# MPBoard_L1_PWR_ext.net
KiCad netlist of a schematic drawn in Altium Designer
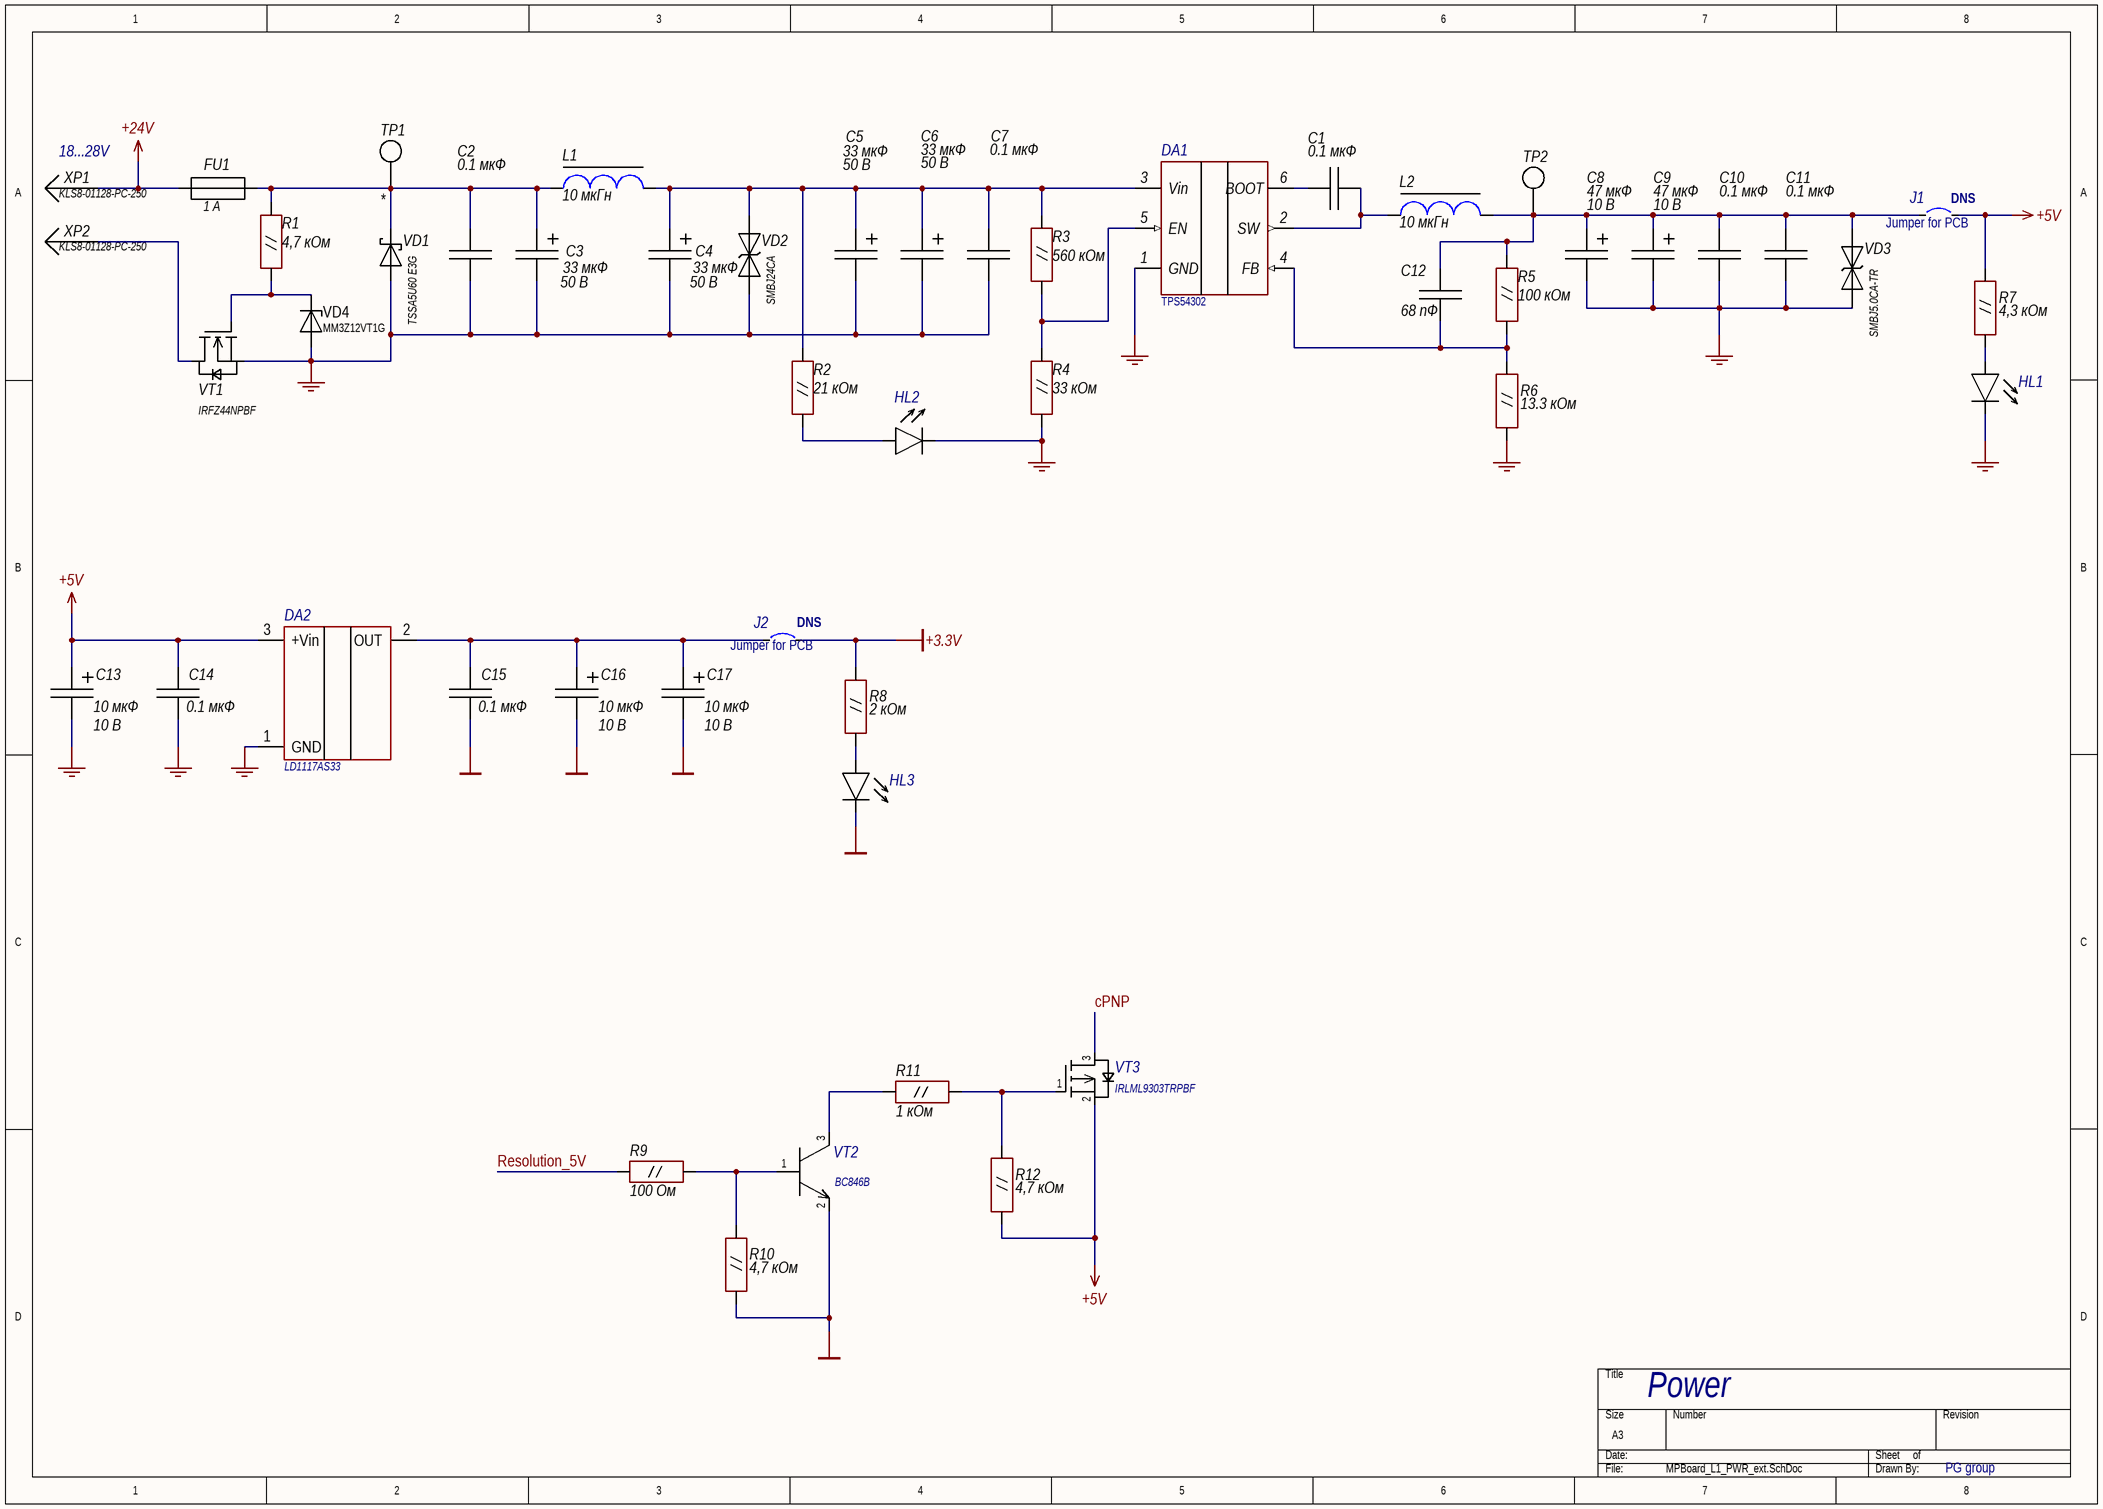
[diagram p0: MPBoard_L1_PWR_ext.SchDoc]

(export (version "E")
  (design (tool "Eeschema 10.0.6"))
  (components
    (comp (ref "C1")
      (value "0.1 мкФ")
      (footprint "CAP-0805")
      (description "Конденсатор")
      (fields (field (name "MF") "KEMET") (field (name "TOLERANCE") "± 10 %"))
      (libsource (lib "MainBoard") (part "C"))
    )
    (comp (ref "C2")
      (value "0.1 мкФ")
      (footprint "CAP-0805")
      (description "Конденсатор")
      (fields (field (name "MF") "KEMET") (field (name "TOLERANCE") "± 10 %"))
      (libsource (lib "MainBoard") (part "C"))
    )
    (comp (ref "C3")
      (value "33 мкФ")
      (footprint "CAPAE-103")
      (description "Конденсатор полярный")
      (fields (field (name "MF") "KEMET") (field (name "TOLERANCE") "± 10 %") (field (name "VOLTAGE") "50 В"))
      (libsource (lib "MainBoard") (part "C_POLAR"))
    )
    (comp (ref "C4")
      (value "33 мкФ")
      (footprint "CAPAE-103")
      (description "Конденсатор полярный")
      (fields (field (name "MF") "KEMET") (field (name "TOLERANCE") "± 10 %") (field (name "VOLTAGE") "50 В"))
      (libsource (lib "MainBoard") (part "C_POLAR"))
    )
    (comp (ref "C5")
      (value "33 мкФ")
      (footprint "CAPAE-103")
      (description "Конденсатор полярный")
      (fields (field (name "MF") "KEMET") (field (name "TOLERANCE") "± 10 %") (field (name "VOLTAGE") "50 В"))
      (libsource (lib "MainBoard") (part "C_POLAR"))
    )
    (comp (ref "C6")
      (value "33 мкФ")
      (footprint "CAPAE-103")
      (description "Конденсатор полярный")
      (fields (field (name "MF") "KEMET") (field (name "TOLERANCE") "± 10 %") (field (name "VOLTAGE") "50 В"))
      (libsource (lib "MainBoard") (part "C_POLAR"))
    )
    (comp (ref "C7")
      (value "0.1 мкФ")
      (footprint "CAP-0805")
      (description "Конденсатор")
      (fields (field (name "MF") "KEMET") (field (name "TOLERANCE") "± 10 %"))
      (libsource (lib "MainBoard") (part "C"))
    )
    (comp (ref "C8")
      (value "47 мкФ")
      (footprint "CAPMP-3528")
      (description "Конденсатор полярный\r\nтантал")
      (fields (field (name "MF") "KEMET") (field (name "TOLERANCE") "± 10 %") (field (name "VOLTAGE") "10 В"))
      (libsource (lib "MainBoard") (part "C_POLAR"))
    )
    (comp (ref "C9")
      (value "47 мкФ")
      (footprint "CAPMP-3528")
      (description "Конденсатор полярный\r\nтантал")
      (fields (field (name "MF") "KEMET") (field (name "TOLERANCE") "± 10 %") (field (name "VOLTAGE") "10 В"))
      (libsource (lib "MainBoard") (part "C_POLAR"))
    )
    (comp (ref "C10")
      (value "0.1 мкФ")
      (footprint "CAP-0805")
      (description "Конденсатор")
      (fields (field (name "MF") "KEMET") (field (name "TOLERANCE") "± 10 %"))
      (libsource (lib "MainBoard") (part "C"))
    )
    (comp (ref "C11")
      (value "0.1 мкФ")
      (footprint "CAP-0805")
      (description "Конденсатор")
      (fields (field (name "MF") "KEMET") (field (name "TOLERANCE") "± 10 %"))
      (libsource (lib "MainBoard") (part "C"))
    )
    (comp (ref "C12")
      (value "68 пФ")
      (footprint "CAP-0805")
      (description "Конденсатор")
      (fields (field (name "MF") "KEMET") (field (name "TOLERANCE") "± 5 %"))
      (libsource (lib "MainBoard") (part "C"))
    )
    (comp (ref "C13")
      (value "10 мкФ")
      (footprint "CAPMP-3528")
      (description "Конденсатор полярный\r\nтантал")
      (fields (field (name "MF") "KEMET") (field (name "TOLERANCE") "± 10 %") (field (name "VOLTAGE") "10 В"))
      (libsource (lib "MainBoard") (part "C_POLAR"))
    )
    (comp (ref "C14")
      (value "0.1 мкФ")
      (footprint "CAP-0805")
      (description "Конденсатор")
      (fields (field (name "MF") "KEMET") (field (name "TOLERANCE") "± 10 %"))
      (libsource (lib "MainBoard") (part "C"))
    )
    (comp (ref "C15")
      (value "0.1 мкФ")
      (footprint "CAP-0805")
      (description "Конденсатор")
      (fields (field (name "MF") "KEMET") (field (name "TOLERANCE") "± 10 %"))
      (libsource (lib "MainBoard") (part "C"))
    )
    (comp (ref "C16")
      (value "10 мкФ")
      (footprint "CAPMP-3528")
      (description "Конденсатор полярный\r\nтантал")
      (fields (field (name "MF") "KEMET") (field (name "TOLERANCE") "± 10 %") (field (name "VOLTAGE") "10 В"))
      (libsource (lib "MainBoard") (part "C_POLAR"))
    )
    (comp (ref "C17")
      (value "10 мкФ")
      (footprint "CAPMP-3528")
      (description "Конденсатор полярный\r\nтантал")
      (fields (field (name "MF") "KEMET") (field (name "TOLERANCE") "± 10 %") (field (name "VOLTAGE") "10 В"))
      (libsource (lib "MainBoard") (part "C_POLAR"))
    )
    (comp (ref "DA1")
      (value "TPS54302")
      (footprint "SOT23-6")
      (description "DC/DC Buck")
      (fields (field (name "MF") "Texas Instruments") (field (name "MFPARTNUM") "TPS54302DDCR"))
      (libsource (lib "MPBoard") (part "DA_TPS54302"))
    )
    (comp (ref "DA2")
      (value "LD1117AS33")
      (footprint "SOT-223 LD1117")
      (description "Linear Regulator 3.3V")
      (fields (field (name "MF") "STMicroelectronics") (field (name "MFPARTNUM") "LD1117AS33TR"))
      (libsource (lib "MPBoard") (part "DA_LD1117AS33"))
    )
    (comp (ref "FU1")
      (value "1 A")
      (footprint "FUSE HOLDERS B 5X20")
      (description "Предохранитель")
      (fields (field (name "MFPARTNUM") "RND 170-00190"))
      (libsource (lib "MPBoard") (part "FU"))
    )
    (comp (ref "HL1")
      (value "Blue")
      (footprint "CH0805LB")
      (description "Светодиод")
      (fields (field (name "MF") "Foryard") (field (name "MFPARTNUM") "FYLS-0805UBC"))
      (libsource (lib "MPBoard") (part "VD_LED"))
    )
    (comp (ref "HL2")
      (value "Red")
      (footprint "CH0805LR")
      (description "Светодиод")
      (fields (field (name "MF") "Foryard") (field (name "MFPARTNUM") "FYLS-0805URC"))
      (libsource (lib "MPBoard") (part "VD_LED"))
    )
    (comp (ref "HL3")
      (value "Green")
      (footprint "CH0805LG")
      (description "Светодиод")
      (fields (field (name "MF") "Foryard") (field (name "MFPARTNUM") "FYLS-0805UGC"))
      (libsource (lib "MPBoard") (part "VD_LED"))
    )
    (comp (ref "J1")
      (value "Jumper for PCB")
      (footprint "JUMPER-SMD min")
      (description "Перемычка на плату")
      (libsource (lib "MPBoard") (part "Jumper"))
    )
    (comp (ref "J2")
      (value "Jumper for PCB")
      (footprint "JUMPER-SMD min")
      (description "Перемычка на плату")
      (libsource (lib "MPBoard") (part "Jumper"))
    )
    (comp (ref "L1")
      (value "10 мкГн")
      (footprint "IND_IHLP2525")
      (description "Индуктивность")
      (fields (field (name "MF") "Vishay") (field (name "MFPARTNUM") "IHLP2525EZER100M01"))
      (libsource (lib "MainBoard") (part "L_CORE"))
    )
    (comp (ref "L2")
      (value "10 мкГн")
      (footprint "IND_IHLP2525")
      (description "Индуктивность")
      (fields (field (name "MF") "Vishay") (field (name "MFPARTNUM") "IHLP2525EZER100M01"))
      (libsource (lib "MainBoard") (part "L_CORE"))
    )
    (comp (ref "R1")
      (value "4,7 кОм")
      (footprint "RES-0805")
      (description "Резистор 0.125 W")
      (fields (field (name "MF") "Vishay") (field (name "TOLERANCE") "± 1 %"))
      (libsource (lib "MainBoard") (part "R_0.125W"))
    )
    (comp (ref "R2")
      (value "21 кОм")
      (footprint "RES-0805")
      (description "Резистор 0.125 W")
      (fields (field (name "MF") "Vishay") (field (name "TOLERANCE") "± 1 %"))
      (libsource (lib "MainBoard") (part "R_0.125W"))
    )
    (comp (ref "R3")
      (value "560 кОм")
      (footprint "RES-0805")
      (description "Резистор 0.125 W")
      (fields (field (name "MF") "Vishay") (field (name "TOLERANCE") "± 5 %"))
      (libsource (lib "") (part "R_0.125W_2"))
    )
    (comp (ref "R4")
      (value "33 кОм")
      (footprint "RES-0805")
      (description "Резистор 0.125 W")
      (fields (field (name "MF") "Vishay") (field (name "TOLERANCE") "± 5 %"))
      (libsource (lib "") (part "R_0.125W_2"))
    )
    (comp (ref "R5")
      (value "100 кОм")
      (footprint "RES-0805")
      (description "Резистор 0.125 W")
      (fields (field (name "MF") "Vishay") (field (name "TOLERANCE") "± 5 %"))
      (libsource (lib "") (part "R_0.125W_2"))
    )
    (comp (ref "R6")
      (value "13.3 кОм")
      (footprint "RES-0805")
      (description "Резистор 0.125 W")
      (fields (field (name "MF") "Vishay") (field (name "TOLERANCE") "± 1 %"))
      (libsource (lib "") (part "R_0.125W_2"))
    )
    (comp (ref "R7")
      (value "4,3 кОм")
      (footprint "RES-0805")
      (description "Резистор 0.125 W")
      (fields (field (name "MF") "Vishay") (field (name "TOLERANCE") "± 1 %"))
      (libsource (lib "") (part "R_0.125W_2"))
    )
    (comp (ref "R8")
      (value "2 кОм")
      (footprint "RES-0805")
      (description "Резистор 0.125 W")
      (fields (field (name "MF") "Vishay") (field (name "TOLERANCE") "± 1 %"))
      (libsource (lib "") (part "R_0.125W_2"))
    )
    (comp (ref "R9")
      (value "100 Ом")
      (footprint "RES-0805")
      (description "Резистор 0.125 W")
      (fields (field (name "MF") "Vishay") (field (name "TOLERANCE") "± 1 %"))
      (libsource (lib "") (part "R_0.125W_1"))
    )
    (comp (ref "R10")
      (value "4,7 кОм")
      (footprint "RES-0805")
      (description "Резистор 0.125 W")
      (fields (field (name "MF") "Vishay") (field (name "TOLERANCE") "± 1 %"))
      (libsource (lib "") (part "R_0.125W_2"))
    )
    (comp (ref "R11")
      (value "1 кОм")
      (footprint "RES-0805")
      (description "Резистор 0.125 W")
      (fields (field (name "MF") "Vishay") (field (name "TOLERANCE") "± 1 %"))
      (libsource (lib "") (part "R_0.125W_1"))
    )
    (comp (ref "R12")
      (value "4,7 кОм")
      (footprint "RES-0805")
      (description "Резистор 0.125 W")
      (fields (field (name "MF") "Vishay") (field (name "TOLERANCE") "± 1 %"))
      (libsource (lib "") (part "R_0.125W_2"))
    )
    (comp (ref "TP1")
      (value "*")
      (footprint "TP_1.5")
      (description "Test Point")
      (libsource (lib "MainBoard") (part "TEST_POINT"))
    )
    (comp (ref "TP2")
      (value "*")
      (footprint "TP_1.5")
      (description "Test Point")
      (libsource (lib "MainBoard") (part "TEST_POINT"))
    )
    (comp (ref "VD1")
      (value "TSSA5U60 E3G")
      (footprint "DIODE SMA")
      (description "Диод Шоттки")
      (fields (field (name "MF") "Taiwan Semiconductor"))
      (libsource (lib "MainBoard") (part "VD_SHOTTKY"))
    )
    (comp (ref "VD2")
      (value "SMBJ24CA")
      (footprint "DIODE SMB")
      (description "Супрессор")
      (fields (field (name "MF") "STMicroelectronics"))
      (libsource (lib "MainBoard") (part "VD_TVS_BIDIR"))
    )
    (comp (ref "VD3")
      (value "SMBJ5.0CA-TR")
      (footprint "DIODE SMB")
      (description "Супрессор")
      (fields (field (name "MF") "STMicroelectronics") (field (name "IPSPARTNUMBER") "300-34-034"))
      (libsource (lib "MainBoard") (part "VD_TVS_BIDIR"))
    )
    (comp (ref "VD4")
      (value "MM3Z12VT1G")
      (footprint "SOD-323")
      (description "Стабилитрон")
      (fields (field (name "MF") "Nexperia"))
      (libsource (lib "MainBoard") (part "VD_ZENER"))
    )
    (comp (ref "VT1")
      (value "IRFZ44NPBF")
      (footprint "TO220S inline")
      (description "MOSFET")
      (fields (field (name "MF") "Infineon Technologies"))
      (libsource (lib "MainBoard") (part "VT_N-MOSFET"))
    )
    (comp (ref "VT2")
      (value "BC846B")
      (footprint "SOT23")
      (description "NPN транзистор")
      (fields (field (name "MF") "Nexperia B.V.") (field (name "MFPARTNUM") "BC846B,215"))
      (libsource (lib "MPBoard") (part "VT_NPN"))
    )
    (comp (ref "VT3")
      (value "IRLML9303TRPBF")
      (footprint "SOT23")
      (description "P-MOSFET")
      (fields (field (name "MF") "INFINEON TECHNOLOGIES AG.") (field (name "VOLTAGE") "30 В"))
      (libsource (lib "MPBoard") (part "VT_P-MOSFET"))
    )
    (comp (ref "XP1")
      (value "KLS8-01128-PC-250")
      (footprint "PCB TAB 4")
      (description "Клемма папа")
      (fields (field (name "MF") "KLS"))
      (libsource (lib "MPBoard") (part "XP1"))
    )
    (comp (ref "XP2")
      (value "KLS8-01128-PC-250")
      (footprint "PCB TAB 4")
      (description "Клемма папа")
      (fields (field (name "MF") "KLS"))
      (libsource (lib "MPBoard") (part "XP1"))
    )
  )
  (nets
    (net (code "1") (name "+3.3V") (class "Default")
      (node (ref "J2") (pin "2") (pintype "passive"))
      (node (ref "R8") (pin "1") (pinfunction "1_1") (pintype "passive"))
    )
    (net (code "2") (name "+5V") (class "Default")
      (node (ref "C13") (pin "1") (pinfunction "1_1") (pintype "passive"))
      (node (ref "C14") (pin "2") (pinfunction "2_2") (pintype "passive"))
      (node (ref "DA2") (pin "3") (pinfunction "+Vin_3") (pintype "power_in"))
      (node (ref "J1") (pin "2") (pintype "passive"))
      (node (ref "R12") (pin "2") (pinfunction "2_2") (pintype "passive"))
      (node (ref "R7") (pin "1") (pinfunction "1_1") (pintype "passive"))
      (node (ref "VT3") (pin "2") (pinfunction "S_2") (pintype "passive"))
    )
    (net (code "3") (name "+24V") (class "Default")
      (node (ref "FU1") (pin "1") (pinfunction "1_1") (pintype "passive"))
      (node (ref "XP1") (pin "1") (pinfunction "1_1") (pintype "passive"))
    )
    (net (code "4") (name "/Resolution_5V") (class "Default")
      (node (ref "R9") (pin "1") (pinfunction "1_1") (pintype "passive"))
    )
    (net (code "5") (name "/cPNP") (class "Default")
      (node (ref "VT3") (pin "3") (pinfunction "D_3") (pintype "passive"))
    )
    (net (code "6") (name "GND") (class "Default")
      (node (ref "C10") (pin "2") (pinfunction "2_2") (pintype "passive"))
      (node (ref "C11") (pin "2") (pinfunction "2_2") (pintype "passive"))
      (node (ref "C13") (pin "2") (pinfunction "2_2") (pintype "passive"))
      (node (ref "C14") (pin "1") (pinfunction "1_1") (pintype "passive"))
      (node (ref "C15") (pin "1") (pinfunction "1_1") (pintype "passive"))
      (node (ref "C16") (pin "2") (pinfunction "2_2") (pintype "passive"))
      (node (ref "C17") (pin "2") (pinfunction "2_2") (pintype "passive"))
      (node (ref "C2") (pin "2") (pinfunction "2_2") (pintype "passive"))
      (node (ref "C3") (pin "2") (pinfunction "2_2") (pintype "passive"))
      (node (ref "C4") (pin "2") (pinfunction "2_2") (pintype "passive"))
      (node (ref "C5") (pin "2") (pinfunction "2_2") (pintype "passive"))
      (node (ref "C6") (pin "2") (pinfunction "2_2") (pintype "passive"))
      (node (ref "C7") (pin "2") (pinfunction "2_2") (pintype "passive"))
      (node (ref "C8") (pin "2") (pinfunction "2_2") (pintype "passive"))
      (node (ref "C9") (pin "2") (pinfunction "2_2") (pintype "passive"))
      (node (ref "DA1") (pin "1") (pinfunction "GND_1") (pintype "power_in"))
      (node (ref "DA2") (pin "1") (pinfunction "GND_1") (pintype "power_in"))
      (node (ref "HL1") (pin "2") (pinfunction "2_2") (pintype "passive"))
      (node (ref "HL2") (pin "2") (pinfunction "2_2") (pintype "passive"))
      (node (ref "HL3") (pin "2") (pinfunction "2_2") (pintype "passive"))
      (node (ref "R10") (pin "2") (pinfunction "2_2") (pintype "passive"))
      (node (ref "R4") (pin "2") (pinfunction "2_2") (pintype "passive"))
      (node (ref "R6") (pin "2") (pinfunction "2_2") (pintype "passive"))
      (node (ref "VD1") (pin "1") (pinfunction "1_1") (pintype "passive"))
      (node (ref "VD2") (pin "1") (pinfunction "1_1") (pintype "passive"))
      (node (ref "VD3") (pin "1") (pinfunction "1_1") (pintype "passive"))
      (node (ref "VD4") (pin "1") (pinfunction "1_1") (pintype "passive"))
      (node (ref "VT1") (pin "3") (pinfunction "S_3") (pintype "passive"))
      (node (ref "VT2") (pin "2") (pinfunction "E_2") (pintype "passive"))
    )
    (net (code "7") (name "Net-(C2-Pad1)") (class "Default")
      (node (ref "C2") (pin "1") (pinfunction "1_1") (pintype "passive"))
      (node (ref "C3") (pin "1") (pinfunction "1_1") (pintype "passive"))
      (node (ref "FU1") (pin "2") (pinfunction "2_2") (pintype "passive"))
      (node (ref "L1") (pin "1") (pinfunction "1_1") (pintype "passive"))
      (node (ref "R1") (pin "2") (pinfunction "2_2") (pintype "passive"))
      (node (ref "TP1") (pin "1") (pinfunction "1_1") (pintype "passive"))
      (node (ref "VD1") (pin "2") (pinfunction "2_2") (pintype "passive"))
    )
    (net (code "8") (name "Net-(C10-Pad1)") (class "Default")
      (node (ref "C10") (pin "1") (pinfunction "1_1") (pintype "passive"))
      (node (ref "C11") (pin "1") (pinfunction "1_1") (pintype "passive"))
      (node (ref "C12") (pin "1") (pinfunction "1_1") (pintype "passive"))
      (node (ref "C8") (pin "1") (pinfunction "1_1") (pintype "passive"))
      (node (ref "C9") (pin "1") (pinfunction "1_1") (pintype "passive"))
      (node (ref "J1") (pin "1") (pintype "passive"))
      (node (ref "L2") (pin "2") (pinfunction "2_2") (pintype "passive"))
      (node (ref "R5") (pin "1") (pinfunction "1_1") (pintype "passive"))
      (node (ref "TP2") (pin "1") (pinfunction "1_1") (pintype "passive"))
      (node (ref "VD3") (pin "2") (pinfunction "2_2") (pintype "passive"))
    )
    (net (code "9") (name "Net-(DA1-BOOT)") (class "Default")
      (node (ref "C1") (pin "1") (pinfunction "1_1") (pintype "passive"))
      (node (ref "DA1") (pin "6") (pinfunction "BOOT_6") (pintype "power_in"))
    )
    (net (code "10") (name "Net-(DA1-EN)") (class "Default")
      (node (ref "DA1") (pin "5") (pinfunction "EN_5") (pintype "input"))
      (node (ref "R3") (pin "2") (pinfunction "2_2") (pintype "passive"))
      (node (ref "R4") (pin "1") (pinfunction "1_1") (pintype "passive"))
    )
    (net (code "11") (name "Net-(DA1-FB)") (class "Default")
      (node (ref "C12") (pin "2") (pinfunction "2_2") (pintype "passive"))
      (node (ref "DA1") (pin "4") (pinfunction "FB_4") (pintype "input"))
      (node (ref "R5") (pin "2") (pinfunction "2_2") (pintype "passive"))
      (node (ref "R6") (pin "1") (pinfunction "1_1") (pintype "passive"))
    )
    (net (code "12") (name "Net-(DA1-SW)") (class "Default")
      (node (ref "C1") (pin "2") (pinfunction "2_2") (pintype "passive"))
      (node (ref "DA1") (pin "2") (pinfunction "SW_2") (pintype "output"))
      (node (ref "L2") (pin "1") (pinfunction "1_1") (pintype "passive"))
    )
    (net (code "13") (name "Net-(DA1-Vin)") (class "Default")
      (node (ref "C4") (pin "1") (pinfunction "1_1") (pintype "passive"))
      (node (ref "C5") (pin "1") (pinfunction "1_1") (pintype "passive"))
      (node (ref "C6") (pin "1") (pinfunction "1_1") (pintype "passive"))
      (node (ref "C7") (pin "1") (pinfunction "1_1") (pintype "passive"))
      (node (ref "DA1") (pin "3") (pinfunction "Vin_3") (pintype "power_in"))
      (node (ref "L1") (pin "2") (pinfunction "2_2") (pintype "passive"))
      (node (ref "R2") (pin "2") (pinfunction "2_2") (pintype "passive"))
      (node (ref "R3") (pin "1") (pinfunction "1_1") (pintype "passive"))
      (node (ref "VD2") (pin "2") (pinfunction "2_2") (pintype "passive"))
    )
    (net (code "14") (name "Net-(DA2-OUT)") (class "Default")
      (node (ref "C15") (pin "2") (pinfunction "2_2") (pintype "passive"))
      (node (ref "C16") (pin "1") (pinfunction "1_1") (pintype "passive"))
      (node (ref "C17") (pin "1") (pinfunction "1_1") (pintype "passive"))
      (node (ref "DA2") (pin "2") (pinfunction "OUT_2") (pintype "power_in"))
      (node (ref "J2") (pin "1") (pintype "passive"))
    )
    (net (code "15") (name "Net-(HL1-Pad1)") (class "Default")
      (node (ref "HL1") (pin "1") (pinfunction "1_1") (pintype "passive"))
      (node (ref "R7") (pin "2") (pinfunction "2_2") (pintype "passive"))
    )
    (net (code "16") (name "Net-(HL2-Pad1)") (class "Default")
      (node (ref "HL2") (pin "1") (pinfunction "1_1") (pintype "passive"))
      (node (ref "R2") (pin "1") (pinfunction "1_1") (pintype "passive"))
    )
    (net (code "17") (name "Net-(HL3-Pad1)") (class "Default")
      (node (ref "HL3") (pin "1") (pinfunction "1_1") (pintype "passive"))
      (node (ref "R8") (pin "2") (pinfunction "2_2") (pintype "passive"))
    )
    (net (code "18") (name "Net-(VT1-D)") (class "Default")
      (node (ref "VT1") (pin "2") (pinfunction "D_2") (pintype "passive"))
      (node (ref "XP2") (pin "1") (pinfunction "1_1") (pintype "passive"))
    )
    (net (code "19") (name "Net-(VT1-G)") (class "Default")
      (node (ref "R1") (pin "1") (pinfunction "1_1") (pintype "passive"))
      (node (ref "VD4") (pin "2") (pinfunction "2_2") (pintype "passive"))
      (node (ref "VT1") (pin "1") (pinfunction "G_1") (pintype "passive"))
    )
    (net (code "20") (name "Net-(VT2-B)") (class "Default")
      (node (ref "R10") (pin "1") (pinfunction "1_1") (pintype "passive"))
      (node (ref "R9") (pin "2") (pinfunction "2_2") (pintype "passive"))
      (node (ref "VT2") (pin "1") (pinfunction "B_1") (pintype "passive"))
    )
    (net (code "21") (name "Net-(VT2-C)") (class "Default")
      (node (ref "R11") (pin "1") (pinfunction "1_1") (pintype "passive"))
      (node (ref "VT2") (pin "3") (pinfunction "C_3") (pintype "passive"))
    )
    (net (code "22") (name "Net-(VT3-G)") (class "Default")
      (node (ref "R11") (pin "2") (pinfunction "2_2") (pintype "passive"))
      (node (ref "R12") (pin "1") (pinfunction "1_1") (pintype "passive"))
      (node (ref "VT3") (pin "1") (pinfunction "G_1") (pintype "passive"))
    )
  )
)
